# ghc-silk.net
KiCad netlist of a schematic drawn in EAGLE
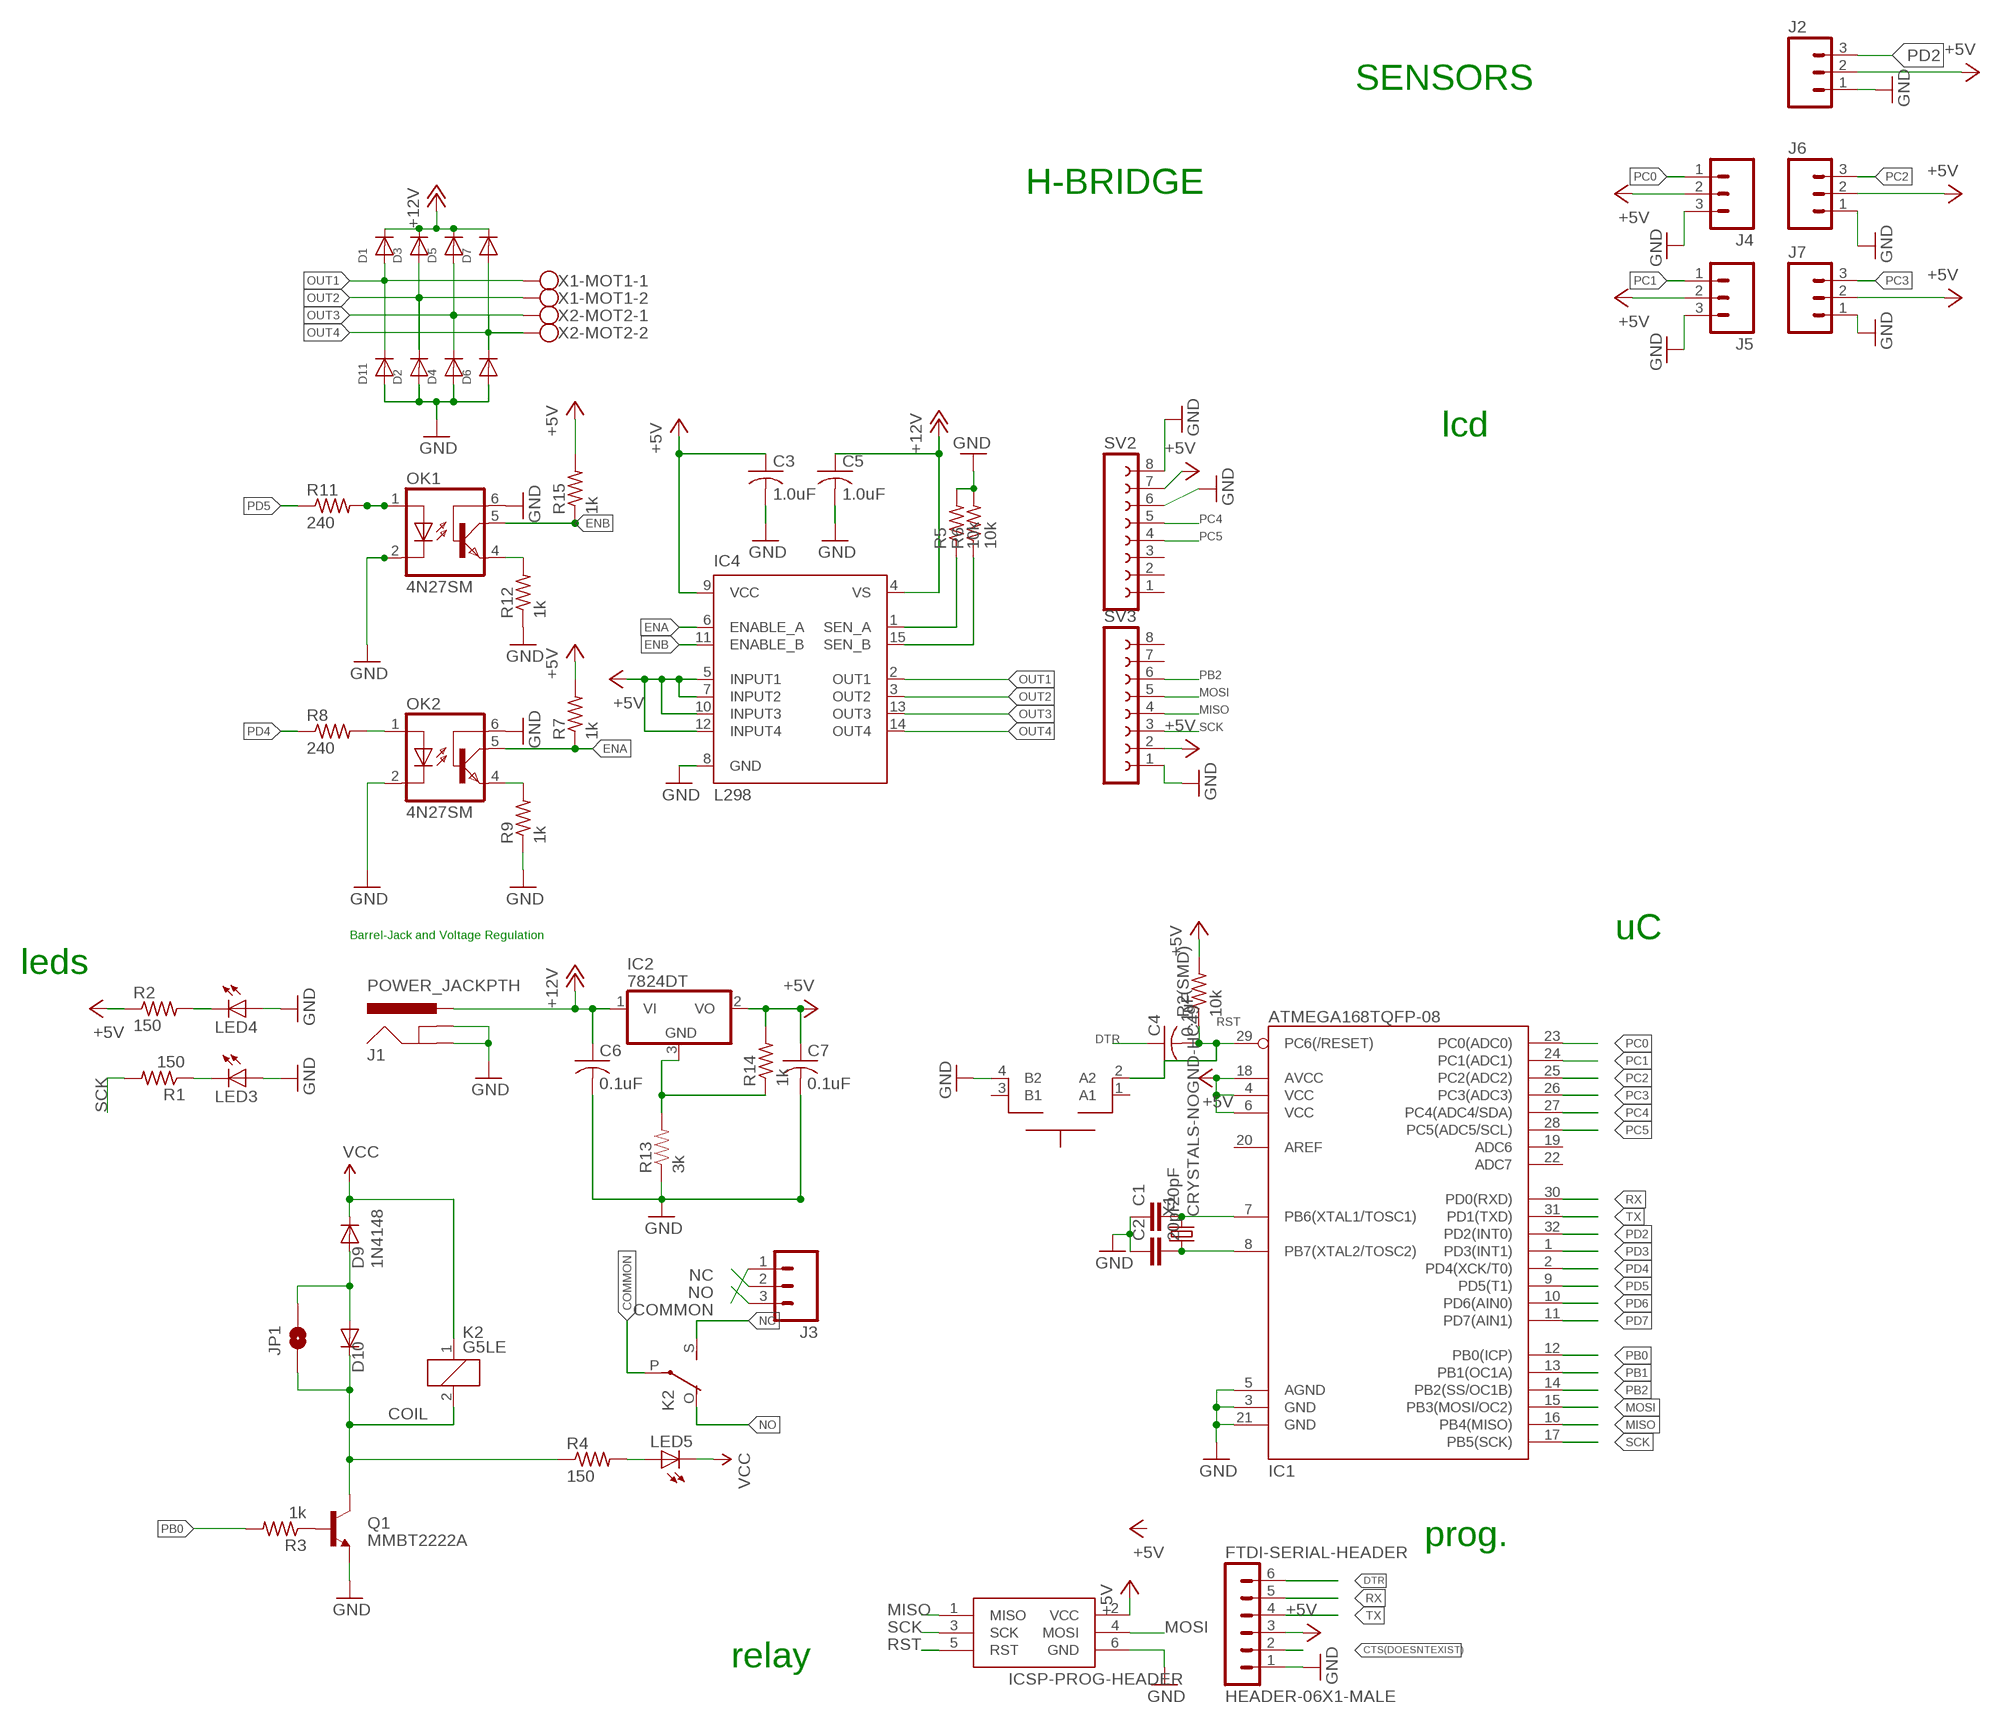
[diagram p0: schematic, sheet 1]

(export (version "E")
  (design (tool "Eeschema 10.0.6"))
  (components
    (comp (ref "C1")
      (value "20pF")
      (footprint "eagle-import:C0805")
      (libsource (lib "eagle-import") (part "C-EUC0805"))
    )
    (comp (ref "C2")
      (value "20pF")
      (footprint "eagle-import:C0805")
      (libsource (lib "eagle-import") (part "C-EUC0805"))
    )
    (comp (ref "C3")
      (value "1.0uF")
      (footprint "eagle-import:C0805")
      (libsource (lib "eagle-import") (part "C-USC0805"))
    )
    (comp (ref "C4")
      (value "0.1uF")
      (footprint "eagle-import:C0805")
      (libsource (lib "eagle-import") (part "C-USC0805"))
    )
    (comp (ref "C5")
      (value "1.0uF")
      (footprint "eagle-import:C0805")
      (libsource (lib "eagle-import") (part "C-USC0805"))
    )
    (comp (ref "C6")
      (value "0.1uF")
      (footprint "eagle-import:C0805")
      (libsource (lib "eagle-import") (part "C-USC0805"))
    )
    (comp (ref "C7")
      (value "0.1uF")
      (footprint "eagle-import:C0805")
      (libsource (lib "eagle-import") (part "C-USC0805"))
    )
    (comp (ref "D1")
      (value "DIODESOD-523")
      (footprint "eagle-import:SOD-523")
      (libsource (lib "eagle-import") (part "DIODESOD-523"))
    )
    (comp (ref "D2")
      (value "DIODESOD-523")
      (footprint "eagle-import:SOD-523")
      (libsource (lib "eagle-import") (part "DIODESOD-523"))
    )
    (comp (ref "D3")
      (value "DIODESOD-523")
      (footprint "eagle-import:SOD-523")
      (libsource (lib "eagle-import") (part "DIODESOD-523"))
    )
    (comp (ref "D4")
      (value "DIODESOD-523")
      (footprint "eagle-import:SOD-523")
      (libsource (lib "eagle-import") (part "DIODESOD-523"))
    )
    (comp (ref "D5")
      (value "DIODESOD-523")
      (footprint "eagle-import:SOD-523")
      (libsource (lib "eagle-import") (part "DIODESOD-523"))
    )
    (comp (ref "D6")
      (value "DIODESOD-523")
      (footprint "eagle-import:SOD-523")
      (libsource (lib "eagle-import") (part "DIODESOD-523"))
    )
    (comp (ref "D7")
      (value "DIODESOD-523")
      (footprint "eagle-import:SOD-523")
      (libsource (lib "eagle-import") (part "DIODESOD-523"))
    )
    (comp (ref "D9")
      (value "1N4148")
      (footprint "eagle-import:SOD-323F")
      (libsource (lib "eagle-import") (part "DIODESOD-323F"))
    )
    (comp (ref "D10")
      (value "Zener")
      (footprint "eagle-import:SOD-323F")
      (libsource (lib "eagle-import") (part "DIODESOD-323F"))
    )
    (comp (ref "D11")
      (value "DIODESOD-523")
      (footprint "eagle-import:SOD-523")
      (libsource (lib "eagle-import") (part "DIODESOD-523"))
    )
    (comp (ref "FTDI-SERIAL-HEADER")
      (value "HEADER-06X1-MALE")
      (footprint "eagle-import:06X1-PTH")
      (libsource (lib "eagle-import") (part "HEADER-06X1?-MALE"))
    )
    (comp (ref "IC1")
      (value "ATMEGA168TQFP-08")
      (footprint "eagle-import:TQFP32-08")
      (libsource (lib "eagle-import") (part "ATMEGA168TQFP-08"))
    )
    (comp (ref "IC2")
      (value "7824DT")
      (footprint "eagle-import:TO252")
      (libsource (lib "eagle-import") (part "78DT24"))
    )
    (comp (ref "IC4")
      (value "L298")
      (footprint "eagle-import:MULTIWATT-15")
      (fields (field (name "MPN") "L298N"))
      (libsource (lib "eagle-import") (part "L298"))
    )
    (comp (ref "ICSP-PROG-HEADER")
      (value "AVRISP-6")
      (footprint "eagle-import:AVRISP")
      (libsource (lib "eagle-import") (part "AVRISP-6"))
    )
    (comp (ref "J1")
      (value "POWER_JACKPTH")
      (footprint "eagle-import:POWER_JACK_PTH")
      (libsource (lib "eagle-import") (part "POWER_JACKPTH"))
    )
    (comp (ref "J2")
      (value "M03SCREW_LOCK")
      (footprint "eagle-import:SCREWTERMINAL-3.5MM-3_LOCK.007S")
      (libsource (lib "eagle-import") (part "M03SCREW_LOCK"))
    )
    (comp (ref "J3")
      (value "M03-SCREW-5MM")
      (footprint "eagle-import:SCREWTERMINAL-5MM-3")
      (libsource (lib "eagle-import") (part "M03-SCREW-5MM"))
    )
    (comp (ref "J4")
      (value "M03SCREW_LOCK")
      (footprint "eagle-import:SCREWTERMINAL-3.5MM-3_LOCK.007S")
      (libsource (lib "eagle-import") (part "M03SCREW_LOCK"))
    )
    (comp (ref "J5")
      (value "M03SCREW_LOCK")
      (footprint "eagle-import:SCREWTERMINAL-3.5MM-3_LOCK.007S")
      (libsource (lib "eagle-import") (part "M03SCREW_LOCK"))
    )
    (comp (ref "J6")
      (value "M03SCREW_LOCK")
      (footprint "eagle-import:SCREWTERMINAL-3.5MM-3_LOCK.007S")
      (libsource (lib "eagle-import") (part "M03SCREW_LOCK"))
    )
    (comp (ref "J7")
      (value "M03SCREW_LOCK")
      (footprint "eagle-import:SCREWTERMINAL-3.5MM-3_LOCK.007S")
      (libsource (lib "eagle-import") (part "M03SCREW_LOCK"))
    )
    (comp (ref "JP1")
      (value "JUMPER-PAD-2-NOYES_SILK")
      (footprint "eagle-import:PAD-JUMPER-2-NO_YES_SILK")
      (libsource (lib "eagle-import") (part "JUMPER-PAD-2-NOYES_SILK"))
    )
    (comp (ref "K2")
      (value "G5LE")
      (footprint "eagle-import:G5LE")
      (libsource (lib "eagle-import") (part "G5LE"))
    )
    (comp (ref "LED3")
      (value "LEDCHIP-LED0805")
      (footprint "eagle-import:CHIP-LED0805")
      (libsource (lib "eagle-import") (part "LEDCHIP-LED0805"))
    )
    (comp (ref "LED4")
      (value "LEDCHIP-LED0805")
      (footprint "eagle-import:CHIP-LED0805")
      (libsource (lib "eagle-import") (part "LEDCHIP-LED0805"))
    )
    (comp (ref "LED5")
      (value "LEDCHIP-LED0805")
      (footprint "eagle-import:CHIP-LED0805")
      (libsource (lib "eagle-import") (part "LEDCHIP-LED0805"))
    )
    (comp (ref "OK1")
      (value "4N27SM")
      (footprint "eagle-import:DIL6-SMD")
      (fields (field (name "MF") "FAIRCHILD SEMICONDUCTOR") (field (name "MPN") "4N27S-M"))
      (libsource (lib "eagle-import") (part "4N?MS27"))
    )
    (comp (ref "OK2")
      (value "4N27SM")
      (footprint "eagle-import:DIL6-SMD")
      (fields (field (name "MF") "FAIRCHILD SEMICONDUCTOR") (field (name "MPN") "4N27S-M"))
      (libsource (lib "eagle-import") (part "4N?MS27"))
    )
    (comp (ref "Q1")
      (value "MMBT2222A")
      (footprint "eagle-import:SOT23-3")
      (libsource (lib "eagle-import") (part "TRANSISTOR_NPNMMBT2222A"))
    )
    (comp (ref "R1")
      (value "150")
      (footprint "eagle-import:M0805")
      (libsource (lib "eagle-import") (part "R-US_M0805"))
    )
    (comp (ref "R2")
      (value "150")
      (footprint "eagle-import:M0805")
      (libsource (lib "eagle-import") (part "R-US_M0805"))
    )
    (comp (ref "R2(SMD)")
      (value "10k")
      (footprint "eagle-import:M0805")
      (libsource (lib "eagle-import") (part "R-US_M0805"))
    )
    (comp (ref "R3")
      (value "1k")
      (footprint "eagle-import:M0805")
      (libsource (lib "eagle-import") (part "R-US_M0805"))
    )
    (comp (ref "R4")
      (value "150")
      (footprint "eagle-import:M0805")
      (libsource (lib "eagle-import") (part "R-US_M0805"))
    )
    (comp (ref "R5")
      (value "10k")
      (footprint "eagle-import:M0805")
      (libsource (lib "eagle-import") (part "R-US_M0805"))
    )
    (comp (ref "R6")
      (value "10k")
      (footprint "eagle-import:M0805")
      (libsource (lib "eagle-import") (part "R-US_M0805"))
    )
    (comp (ref "R7")
      (value "1k")
      (footprint "eagle-import:M0805")
      (libsource (lib "eagle-import") (part "R-US_M0805"))
    )
    (comp (ref "R8")
      (value "240")
      (footprint "eagle-import:M0805")
      (libsource (lib "eagle-import") (part "R-US_M0805"))
    )
    (comp (ref "R9")
      (value "1k")
      (footprint "eagle-import:M0805")
      (libsource (lib "eagle-import") (part "R-US_M0805"))
    )
    (comp (ref "R11")
      (value "240")
      (footprint "eagle-import:M0805")
      (libsource (lib "eagle-import") (part "R-US_M0805"))
    )
    (comp (ref "R12")
      (value "1k")
      (footprint "eagle-import:M0805")
      (libsource (lib "eagle-import") (part "R-US_M0805"))
    )
    (comp (ref "R13")
      (value "3k")
      (footprint "eagle-import:0402-RES")
      (libsource (lib "eagle-import") (part "RESISTOR0402"))
    )
    (comp (ref "R14")
      (value "1k")
      (footprint "eagle-import:M0805")
      (libsource (lib "eagle-import") (part "R-US_M0805"))
    )
    (comp (ref "R15")
      (value "1k")
      (footprint "eagle-import:M0805")
      (libsource (lib "eagle-import") (part "R-US_M0805"))
    )
    (comp (ref "SV2")
      (value "FE08-1")
      (footprint "eagle-import:FE08")
      (libsource (lib "eagle-import") (part "FE08-1"))
    )
    (comp (ref "SV3")
      (value "FE08-1")
      (footprint "eagle-import:FE08")
      (libsource (lib "eagle-import") (part "FE08-1"))
    )
    (comp (ref "SW2")
      (value "MOMENTARYBUTTON")
      (footprint "eagle-import:SPST_NO_SMD")
      (libsource (lib "eagle-import") (part "MOMENTARYBUTTON"))
    )
    (comp (ref "X1")
      (value "CRYSTALS-NOGND-HC49")
      (footprint "eagle-import:HC49")
      (libsource (lib "eagle-import") (part "CRYSTALS-NOGND-HC49"))
    )
    (comp (ref "X1-MOT1")
      (value "W237-102")
      (footprint "eagle-import:W237-102")
      (fields (field (name "MPN") "237-102"))
      (libsource (lib "eagle-import") (part "W237-102"))
    )
    (comp (ref "X2-MOT2")
      (value "W237-102")
      (footprint "eagle-import:W237-102")
      (fields (field (name "MPN") "237-102"))
      (libsource (lib "eagle-import") (part "W237-102"))
    )
  )
  (nets
    (net (code "1") (name "+5V") (class "Default")
      (node (ref "C3") (pin "1") (pinfunction "1_1") (pintype "passive"))
      (node (ref "C7") (pin "1") (pinfunction "1_1") (pintype "passive"))
      (node (ref "FTDI-SERIAL-HEADER") (pin "3") (pinfunction "3_3") (pintype "passive"))
      (node (ref "IC1") (pin "18") (pinfunction "AVCC_18") (pintype "bidirectional"))
      (node (ref "IC1") (pin "4") (pinfunction "VCC_4") (pintype "bidirectional"))
      (node (ref "IC1") (pin "6") (pinfunction "VCC_6") (pintype "bidirectional"))
      (node (ref "IC2") (pin "2") (pinfunction "VO_2") (pintype "passive"))
      (node (ref "IC4") (pin "10") (pinfunction "INPUT3_10") (pintype "input"))
      (node (ref "IC4") (pin "12") (pinfunction "INPUT4_12") (pintype "input"))
      (node (ref "IC4") (pin "5") (pinfunction "INPUT1_5") (pintype "input"))
      (node (ref "IC4") (pin "7") (pinfunction "INPUT2_7") (pintype "input"))
      (node (ref "IC4") (pin "9") (pinfunction "VCC_9") (pintype "power_in"))
      (node (ref "ICSP-PROG-HEADER") (pin "2") (pinfunction "VCC_2") (pintype "power_in"))
      (node (ref "J2") (pin "2") (pinfunction "2_2") (pintype "passive"))
      (node (ref "J4") (pin "2") (pinfunction "2_2") (pintype "passive"))
      (node (ref "J5") (pin "2") (pinfunction "2_2") (pintype "passive"))
      (node (ref "J6") (pin "2") (pinfunction "2_2") (pintype "passive"))
      (node (ref "J7") (pin "2") (pinfunction "2_2") (pintype "passive"))
      (node (ref "R14") (pin "2") (pinfunction "2_2") (pintype "passive"))
      (node (ref "R15") (pin "2") (pinfunction "2_2") (pintype "passive"))
      (node (ref "R2") (pin "1") (pinfunction "1_1") (pintype "passive"))
      (node (ref "R2(SMD)") (pin "2") (pinfunction "2_2") (pintype "passive"))
      (node (ref "R7") (pin "2") (pinfunction "2_2") (pintype "passive"))
      (node (ref "SV2") (pin "7") (pinfunction "7_7") (pintype "passive"))
      (node (ref "SV3") (pin "2") (pinfunction "2_2") (pintype "passive"))
    )
    (net (code "2") (name "+12V") (class "Default")
      (node (ref "C5") (pin "1") (pinfunction "1_1") (pintype "passive"))
      (node (ref "C6") (pin "1") (pinfunction "1_1") (pintype "passive"))
      (node (ref "D1") (pin "K") (pinfunction "C_K") (pintype "passive"))
      (node (ref "D3") (pin "K") (pinfunction "C_K") (pintype "passive"))
      (node (ref "D5") (pin "K") (pinfunction "C_K") (pintype "passive"))
      (node (ref "D7") (pin "K") (pinfunction "C_K") (pintype "passive"))
      (node (ref "IC2") (pin "1") (pinfunction "VI_1") (pintype "input"))
      (node (ref "IC4") (pin "4") (pinfunction "VS_4") (pintype "power_in"))
      (node (ref "J1") (pin "PWR") (pinfunction "PWR_PWR") (pintype "bidirectional"))
    )
    (net (code "3") (name "/COIL") (class "Default")
      (node (ref "D10") (pin "C") (pinfunction "C_C") (pintype "passive"))
      (node (ref "JP1") (pin "1") (pinfunction "1_1") (pintype "passive"))
      (node (ref "K2") (pin "2") (pinfunction "2_2") (pintype "passive"))
      (node (ref "Q1") (pin "3") (pinfunction "C_3") (pintype "passive"))
      (node (ref "R4") (pin "1") (pinfunction "1_1") (pintype "passive"))
    )
    (net (code "4") (name "/RST") (class "Default")
      (node (ref "C4") (pin "2") (pinfunction "2_2") (pintype "passive"))
      (node (ref "IC1") (pin "29") (pinfunction "PC6(/RESET)_29") (pintype "bidirectional"))
      (node (ref "ICSP-PROG-HEADER") (pin "5") (pinfunction "RST_5") (pintype "output"))
      (node (ref "R2(SMD)") (pin "1") (pinfunction "1_1") (pintype "passive"))
      (node (ref "SW2") (pin "2") (pinfunction "A2_2") (pintype "bidirectional"))
    )
    (net (code "5") (name "COMMON") (class "Default")
      (node (ref "J3") (pin "1") (pinfunction "1_1") (pintype "passive"))
      (node (ref "K2") (pin "P") (pinfunction "P_P") (pintype "passive"))
    )
    (net (code "6") (name "CTS(DOESNTEXIST)") (class "Default")
      (node (ref "FTDI-SERIAL-HEADER") (pin "2") (pinfunction "2_2") (pintype "passive"))
    )
    (net (code "7") (name "DTR") (class "Default")
      (node (ref "C4") (pin "1") (pinfunction "1_1") (pintype "passive"))
      (node (ref "FTDI-SERIAL-HEADER") (pin "6") (pinfunction "6_6") (pintype "passive"))
    )
    (net (code "8") (name "ENA") (class "Default")
      (node (ref "IC4") (pin "6") (pinfunction "ENABLE_A_6") (pintype "input"))
      (node (ref "OK2") (pin "5") (pinfunction "COL_5") (pintype "passive"))
      (node (ref "R7") (pin "1") (pinfunction "1_1") (pintype "passive"))
    )
    (net (code "9") (name "ENB") (class "Default")
      (node (ref "IC4") (pin "11") (pinfunction "ENABLE_B_11") (pintype "input"))
      (node (ref "OK1") (pin "5") (pinfunction "COL_5") (pintype "passive"))
      (node (ref "R15") (pin "1") (pinfunction "1_1") (pintype "passive"))
    )
    (net (code "10") (name "GND") (class "Default")
      (node (ref "C1") (pin "1") (pinfunction "1_1") (pintype "passive"))
      (node (ref "C2") (pin "1") (pinfunction "1_1") (pintype "passive"))
      (node (ref "C3") (pin "2") (pinfunction "2_2") (pintype "passive"))
      (node (ref "C5") (pin "2") (pinfunction "2_2") (pintype "passive"))
      (node (ref "C6") (pin "2") (pinfunction "2_2") (pintype "passive"))
      (node (ref "C7") (pin "2") (pinfunction "2_2") (pintype "passive"))
      (node (ref "D11") (pin "A") (pinfunction "A_A") (pintype "passive"))
      (node (ref "D2") (pin "A") (pinfunction "A_A") (pintype "passive"))
      (node (ref "D4") (pin "A") (pinfunction "A_A") (pintype "passive"))
      (node (ref "D6") (pin "A") (pinfunction "A_A") (pintype "passive"))
      (node (ref "FTDI-SERIAL-HEADER") (pin "1") (pinfunction "1_1") (pintype "passive"))
      (node (ref "IC1") (pin "21") (pinfunction "GND_21") (pintype "bidirectional"))
      (node (ref "IC1") (pin "3") (pinfunction "GND_3") (pintype "bidirectional"))
      (node (ref "IC1") (pin "5") (pinfunction "AGND_5") (pintype "bidirectional"))
      (node (ref "IC4") (pin "8") (pinfunction "GND_8") (pintype "power_in"))
      (node (ref "ICSP-PROG-HEADER") (pin "6") (pinfunction "GND_6") (pintype "power_in"))
      (node (ref "J1") (pin "GND") (pinfunction "GND_GND") (pintype "bidirectional"))
      (node (ref "J1") (pin "GNDBREAK") (pinfunction "GNDBREAK_GNDBREAK") (pintype "bidirectional"))
      (node (ref "J2") (pin "1") (pinfunction "1_1") (pintype "passive"))
      (node (ref "J4") (pin "3") (pinfunction "3_3") (pintype "passive"))
      (node (ref "J5") (pin "3") (pinfunction "3_3") (pintype "passive"))
      (node (ref "J6") (pin "1") (pinfunction "1_1") (pintype "passive"))
      (node (ref "J7") (pin "1") (pinfunction "1_1") (pintype "passive"))
      (node (ref "LED3") (pin "A") (pinfunction "A_A") (pintype "passive"))
      (node (ref "LED4") (pin "A") (pinfunction "A_A") (pintype "passive"))
      (node (ref "OK1") (pin "2") (pinfunction "C_2") (pintype "passive"))
      (node (ref "OK1") (pin "6") (pinfunction "BAS_6") (pintype "passive"))
      (node (ref "OK2") (pin "2") (pinfunction "C_2") (pintype "passive"))
      (node (ref "OK2") (pin "6") (pinfunction "BAS_6") (pintype "passive"))
      (node (ref "Q1") (pin "2") (pinfunction "E_2") (pintype "passive"))
      (node (ref "R12") (pin "1") (pinfunction "1_1") (pintype "passive"))
      (node (ref "R13") (pin "1") (pinfunction "1_1") (pintype "passive"))
      (node (ref "R5") (pin "2") (pinfunction "2_2") (pintype "passive"))
      (node (ref "R6") (pin "2") (pinfunction "2_2") (pintype "passive"))
      (node (ref "R9") (pin "1") (pinfunction "1_1") (pintype "passive"))
      (node (ref "SV2") (pin "6") (pinfunction "6_6") (pintype "passive"))
      (node (ref "SV2") (pin "8") (pinfunction "8_8") (pintype "passive"))
      (node (ref "SV3") (pin "1") (pinfunction "1_1") (pintype "passive"))
      (node (ref "SW2") (pin "4") (pinfunction "B2_4") (pintype "bidirectional"))
    )
    (net (code "11") (name "MISO") (class "Default")
      (node (ref "IC1") (pin "16") (pinfunction "PB4(MISO)_16") (pintype "bidirectional"))
      (node (ref "ICSP-PROG-HEADER") (pin "1") (pinfunction "MISO_1") (pintype "input"))
      (node (ref "SV3") (pin "4") (pinfunction "4_4") (pintype "passive"))
    )
    (net (code "12") (name "MOSI") (class "Default")
      (node (ref "IC1") (pin "15") (pinfunction "PB3(MOSI/OC2)_15") (pintype "bidirectional"))
      (node (ref "ICSP-PROG-HEADER") (pin "4") (pinfunction "MOSI_4") (pintype "output"))
      (node (ref "SV3") (pin "5") (pinfunction "5_5") (pintype "passive"))
    )
    (net (code "13") (name "NC") (class "Default")
      (node (ref "J3") (pin "2") (pinfunction "2_2") (pintype "passive"))
      (node (ref "K2") (pin "S") (pinfunction "S_S") (pintype "passive"))
    )
    (net (code "14") (name "NO") (class "Default")
      (node (ref "J3") (pin "3") (pinfunction "3_3") (pintype "passive"))
      (node (ref "K2") (pin "O") (pinfunction "O_O") (pintype "passive"))
    )
    (net (code "15") (name "Net-(D10-PadA)") (class "Default")
      (node (ref "D10") (pin "A") (pinfunction "A_A") (pintype "passive"))
      (node (ref "D9") (pin "A") (pinfunction "A_A") (pintype "passive"))
      (node (ref "JP1") (pin "2") (pinfunction "2_2") (pintype "passive"))
    )
    (net (code "16") (name "Net-(IC1-PB6(XTAL1{slash}TOSC1))") (class "Default")
      (node (ref "C1") (pin "2") (pinfunction "2_2") (pintype "passive"))
      (node (ref "IC1") (pin "7") (pinfunction "PB6(XTAL1/TOSC1)_7") (pintype "bidirectional"))
      (node (ref "X1") (pin "2") (pinfunction "2_2") (pintype "passive"))
    )
    (net (code "17") (name "Net-(IC1-PB7(XTAL2{slash}TOSC2))") (class "Default")
      (node (ref "C2") (pin "2") (pinfunction "2_2") (pintype "passive"))
      (node (ref "IC1") (pin "8") (pinfunction "PB7(XTAL2/TOSC2)_8") (pintype "bidirectional"))
      (node (ref "X1") (pin "1") (pinfunction "1_1") (pintype "passive"))
    )
    (net (code "18") (name "Net-(IC2-GND)") (class "Default")
      (node (ref "IC2") (pin "3") (pinfunction "GND_3") (pintype "passive"))
      (node (ref "R13") (pin "2") (pinfunction "2_2") (pintype "passive"))
      (node (ref "R14") (pin "1") (pinfunction "1_1") (pintype "passive"))
    )
    (net (code "19") (name "Net-(IC4-SEN_A)") (class "Default")
      (node (ref "IC4") (pin "1") (pinfunction "SEN_A_1") (pintype "input"))
      (node (ref "R5") (pin "1") (pinfunction "1_1") (pintype "passive"))
    )
    (net (code "20") (name "Net-(IC4-SEN_B)") (class "Default")
      (node (ref "IC4") (pin "15") (pinfunction "SEN_B_15") (pintype "input"))
      (node (ref "R6") (pin "1") (pinfunction "1_1") (pintype "passive"))
    )
    (net (code "21") (name "Net-(LED3-PadC)") (class "Default")
      (node (ref "LED3") (pin "C") (pinfunction "C_C") (pintype "passive"))
      (node (ref "R1") (pin "1") (pinfunction "1_1") (pintype "passive"))
    )
    (net (code "22") (name "Net-(LED4-PadC)") (class "Default")
      (node (ref "LED4") (pin "C") (pinfunction "C_C") (pintype "passive"))
      (node (ref "R2") (pin "2") (pinfunction "2_2") (pintype "passive"))
    )
    (net (code "23") (name "Net-(LED5-PadA)") (class "Default")
      (node (ref "LED5") (pin "A") (pinfunction "A_A") (pintype "passive"))
      (node (ref "R4") (pin "2") (pinfunction "2_2") (pintype "passive"))
    )
    (net (code "24") (name "Net-(OK1-A)") (class "Default")
      (node (ref "OK1") (pin "1") (pinfunction "A_1") (pintype "passive"))
      (node (ref "R11") (pin "2") (pinfunction "2_2") (pintype "passive"))
    )
    (net (code "25") (name "Net-(OK1-EMI)") (class "Default")
      (node (ref "OK1") (pin "4") (pinfunction "EMI_4") (pintype "passive"))
      (node (ref "R12") (pin "2") (pinfunction "2_2") (pintype "passive"))
    )
    (net (code "26") (name "Net-(OK2-A)") (class "Default")
      (node (ref "OK2") (pin "1") (pinfunction "A_1") (pintype "passive"))
      (node (ref "R8") (pin "2") (pinfunction "2_2") (pintype "passive"))
    )
    (net (code "27") (name "Net-(OK2-EMI)") (class "Default")
      (node (ref "OK2") (pin "4") (pinfunction "EMI_4") (pintype "passive"))
      (node (ref "R9") (pin "2") (pinfunction "2_2") (pintype "passive"))
    )
    (net (code "28") (name "Net-(Q1-B)") (class "Default")
      (node (ref "Q1") (pin "1") (pinfunction "B_1") (pintype "passive"))
      (node (ref "R3") (pin "1") (pinfunction "1_1") (pintype "passive"))
    )
    (net (code "29") (name "OUT1") (class "Default")
      (node (ref "D1") (pin "A") (pinfunction "A_A") (pintype "passive"))
      (node (ref "D11") (pin "K") (pinfunction "C_K") (pintype "passive"))
      (node (ref "IC4") (pin "2") (pinfunction "OUT1_2") (pintype "output"))
      (node (ref "X1-MOT1") (pin "1") (pinfunction "KL_1") (pintype "passive"))
    )
    (net (code "30") (name "OUT2") (class "Default")
      (node (ref "D2") (pin "K") (pinfunction "C_K") (pintype "passive"))
      (node (ref "D3") (pin "A") (pinfunction "A_A") (pintype "passive"))
      (node (ref "IC4") (pin "3") (pinfunction "OUT2_3") (pintype "output"))
      (node (ref "X1-MOT1") (pin "2") (pinfunction "KL_2") (pintype "passive"))
    )
    (net (code "31") (name "OUT3") (class "Default")
      (node (ref "D4") (pin "K") (pinfunction "C_K") (pintype "passive"))
      (node (ref "D5") (pin "A") (pinfunction "A_A") (pintype "passive"))
      (node (ref "IC4") (pin "13") (pinfunction "OUT3_13") (pintype "output"))
      (node (ref "X2-MOT2") (pin "1") (pinfunction "KL_1") (pintype "passive"))
    )
    (net (code "32") (name "OUT4") (class "Default")
      (node (ref "D6") (pin "K") (pinfunction "C_K") (pintype "passive"))
      (node (ref "D7") (pin "A") (pinfunction "A_A") (pintype "passive"))
      (node (ref "IC4") (pin "14") (pinfunction "OUT4_14") (pintype "output"))
      (node (ref "X2-MOT2") (pin "2") (pinfunction "KL_2") (pintype "passive"))
    )
    (net (code "33") (name "PB0") (class "Default")
      (node (ref "IC1") (pin "12") (pinfunction "PB0(ICP)_12") (pintype "bidirectional"))
      (node (ref "R3") (pin "2") (pinfunction "2_2") (pintype "passive"))
    )
    (net (code "34") (name "PB1") (class "Default")
      (node (ref "IC1") (pin "13") (pinfunction "PB1(OC1A)_13") (pintype "bidirectional"))
    )
    (net (code "35") (name "PB2") (class "Default")
      (node (ref "IC1") (pin "14") (pinfunction "PB2(SS/OC1B)_14") (pintype "bidirectional"))
      (node (ref "SV3") (pin "6") (pinfunction "6_6") (pintype "passive"))
    )
    (net (code "36") (name "PC0") (class "Default")
      (node (ref "IC1") (pin "23") (pinfunction "PC0(ADC0)_23") (pintype "bidirectional"))
      (node (ref "J4") (pin "1") (pinfunction "1_1") (pintype "passive"))
    )
    (net (code "37") (name "PC1") (class "Default")
      (node (ref "IC1") (pin "24") (pinfunction "PC1(ADC1)_24") (pintype "bidirectional"))
      (node (ref "J5") (pin "1") (pinfunction "1_1") (pintype "passive"))
    )
    (net (code "38") (name "PC2") (class "Default")
      (node (ref "IC1") (pin "25") (pinfunction "PC2(ADC2)_25") (pintype "bidirectional"))
      (node (ref "J6") (pin "3") (pinfunction "3_3") (pintype "passive"))
    )
    (net (code "39") (name "PC3") (class "Default")
      (node (ref "IC1") (pin "26") (pinfunction "PC3(ADC3)_26") (pintype "bidirectional"))
      (node (ref "J7") (pin "3") (pinfunction "3_3") (pintype "passive"))
    )
    (net (code "40") (name "PC4") (class "Default")
      (node (ref "IC1") (pin "27") (pinfunction "PC4(ADC4/SDA)_27") (pintype "bidirectional"))
      (node (ref "SV2") (pin "5") (pinfunction "5_5") (pintype "passive"))
    )
    (net (code "41") (name "PC5") (class "Default")
      (node (ref "IC1") (pin "28") (pinfunction "PC5(ADC5/SCL)_28") (pintype "bidirectional"))
      (node (ref "SV2") (pin "4") (pinfunction "4_4") (pintype "passive"))
    )
    (net (code "42") (name "PD2") (class "Default")
      (node (ref "IC1") (pin "32") (pinfunction "PD2(INT0)_32") (pintype "bidirectional"))
      (node (ref "J2") (pin "3") (pinfunction "3_3") (pintype "passive"))
    )
    (net (code "43") (name "PD3") (class "Default")
      (node (ref "IC1") (pin "1") (pinfunction "PD3(INT1)_1") (pintype "bidirectional"))
    )
    (net (code "44") (name "PD4") (class "Default")
      (node (ref "IC1") (pin "2") (pinfunction "PD4(XCK/T0)_2") (pintype "bidirectional"))
      (node (ref "R8") (pin "1") (pinfunction "1_1") (pintype "passive"))
    )
    (net (code "45") (name "PD5") (class "Default")
      (node (ref "IC1") (pin "9") (pinfunction "PD5(T1)_9") (pintype "bidirectional"))
      (node (ref "R11") (pin "1") (pinfunction "1_1") (pintype "passive"))
    )
    (net (code "46") (name "PD6") (class "Default")
      (node (ref "IC1") (pin "10") (pinfunction "PD6(AIN0)_10") (pintype "bidirectional"))
    )
    (net (code "47") (name "PD7") (class "Default")
      (node (ref "IC1") (pin "11") (pinfunction "PD7(AIN1)_11") (pintype "bidirectional"))
    )
    (net (code "48") (name "RX") (class "Default")
      (node (ref "FTDI-SERIAL-HEADER") (pin "5") (pinfunction "5_5") (pintype "passive"))
      (node (ref "IC1") (pin "30") (pinfunction "PD0(RXD)_30") (pintype "bidirectional"))
    )
    (net (code "49") (name "SCK") (class "Default")
      (node (ref "IC1") (pin "17") (pinfunction "PB5(SCK)_17") (pintype "bidirectional"))
      (node (ref "ICSP-PROG-HEADER") (pin "3") (pinfunction "SCK_3") (pintype "output"))
      (node (ref "R1") (pin "2") (pinfunction "2_2") (pintype "passive"))
      (node (ref "SV3") (pin "3") (pinfunction "3_3") (pintype "passive"))
    )
    (net (code "50") (name "TX") (class "Default")
      (node (ref "FTDI-SERIAL-HEADER") (pin "4") (pinfunction "4_4") (pintype "passive"))
      (node (ref "IC1") (pin "31") (pinfunction "PD1(TXD)_31") (pintype "bidirectional"))
    )
    (net (code "51") (name "VCC") (class "Default")
      (node (ref "D9") (pin "C") (pinfunction "C_C") (pintype "passive"))
      (node (ref "K2") (pin "1") (pinfunction "1_1") (pintype "passive"))
      (node (ref "LED5") (pin "C") (pinfunction "C_C") (pintype "passive"))
    )
    (net (code "52") (name "unconnected-(IC1-ADC6-Pad19)") (class "Default")
      (node (ref "IC1") (pin "19") (pinfunction "ADC6_19") (pintype "bidirectional"))
    )
    (net (code "53") (name "unconnected-(IC1-ADC7-Pad22)") (class "Default")
      (node (ref "IC1") (pin "22") (pinfunction "ADC7_22") (pintype "bidirectional"))
    )
    (net (code "54") (name "unconnected-(IC1-AREF-Pad20)") (class "Default")
      (node (ref "IC1") (pin "20") (pinfunction "AREF_20") (pintype "bidirectional"))
    )
    (net (code "55") (name "unconnected-(SV2-Pad1)") (class "Default")
      (node (ref "SV2") (pin "1") (pinfunction "1_1") (pintype "passive"))
    )
    (net (code "56") (name "unconnected-(SV2-Pad2)") (class "Default")
      (node (ref "SV2") (pin "2") (pinfunction "2_2") (pintype "passive"))
    )
    (net (code "57") (name "unconnected-(SV2-Pad3)") (class "Default")
      (node (ref "SV2") (pin "3") (pinfunction "3_3") (pintype "passive"))
    )
    (net (code "58") (name "unconnected-(SV3-Pad7)") (class "Default")
      (node (ref "SV3") (pin "7") (pinfunction "7_7") (pintype "passive"))
    )
    (net (code "59") (name "unconnected-(SV3-Pad8)") (class "Default")
      (node (ref "SV3") (pin "8") (pinfunction "8_8") (pintype "passive"))
    )
    (net (code "60") (name "unconnected-(SW2-A1-Pad1)") (class "Default")
      (node (ref "SW2") (pin "1") (pinfunction "A1_1") (pintype "bidirectional"))
    )
    (net (code "61") (name "unconnected-(SW2-B1-Pad3)") (class "Default")
      (node (ref "SW2") (pin "3") (pinfunction "B1_3") (pintype "bidirectional"))
    )
  )
)
